# lid.net
KiCad netlist of a schematic drawn in EAGLE
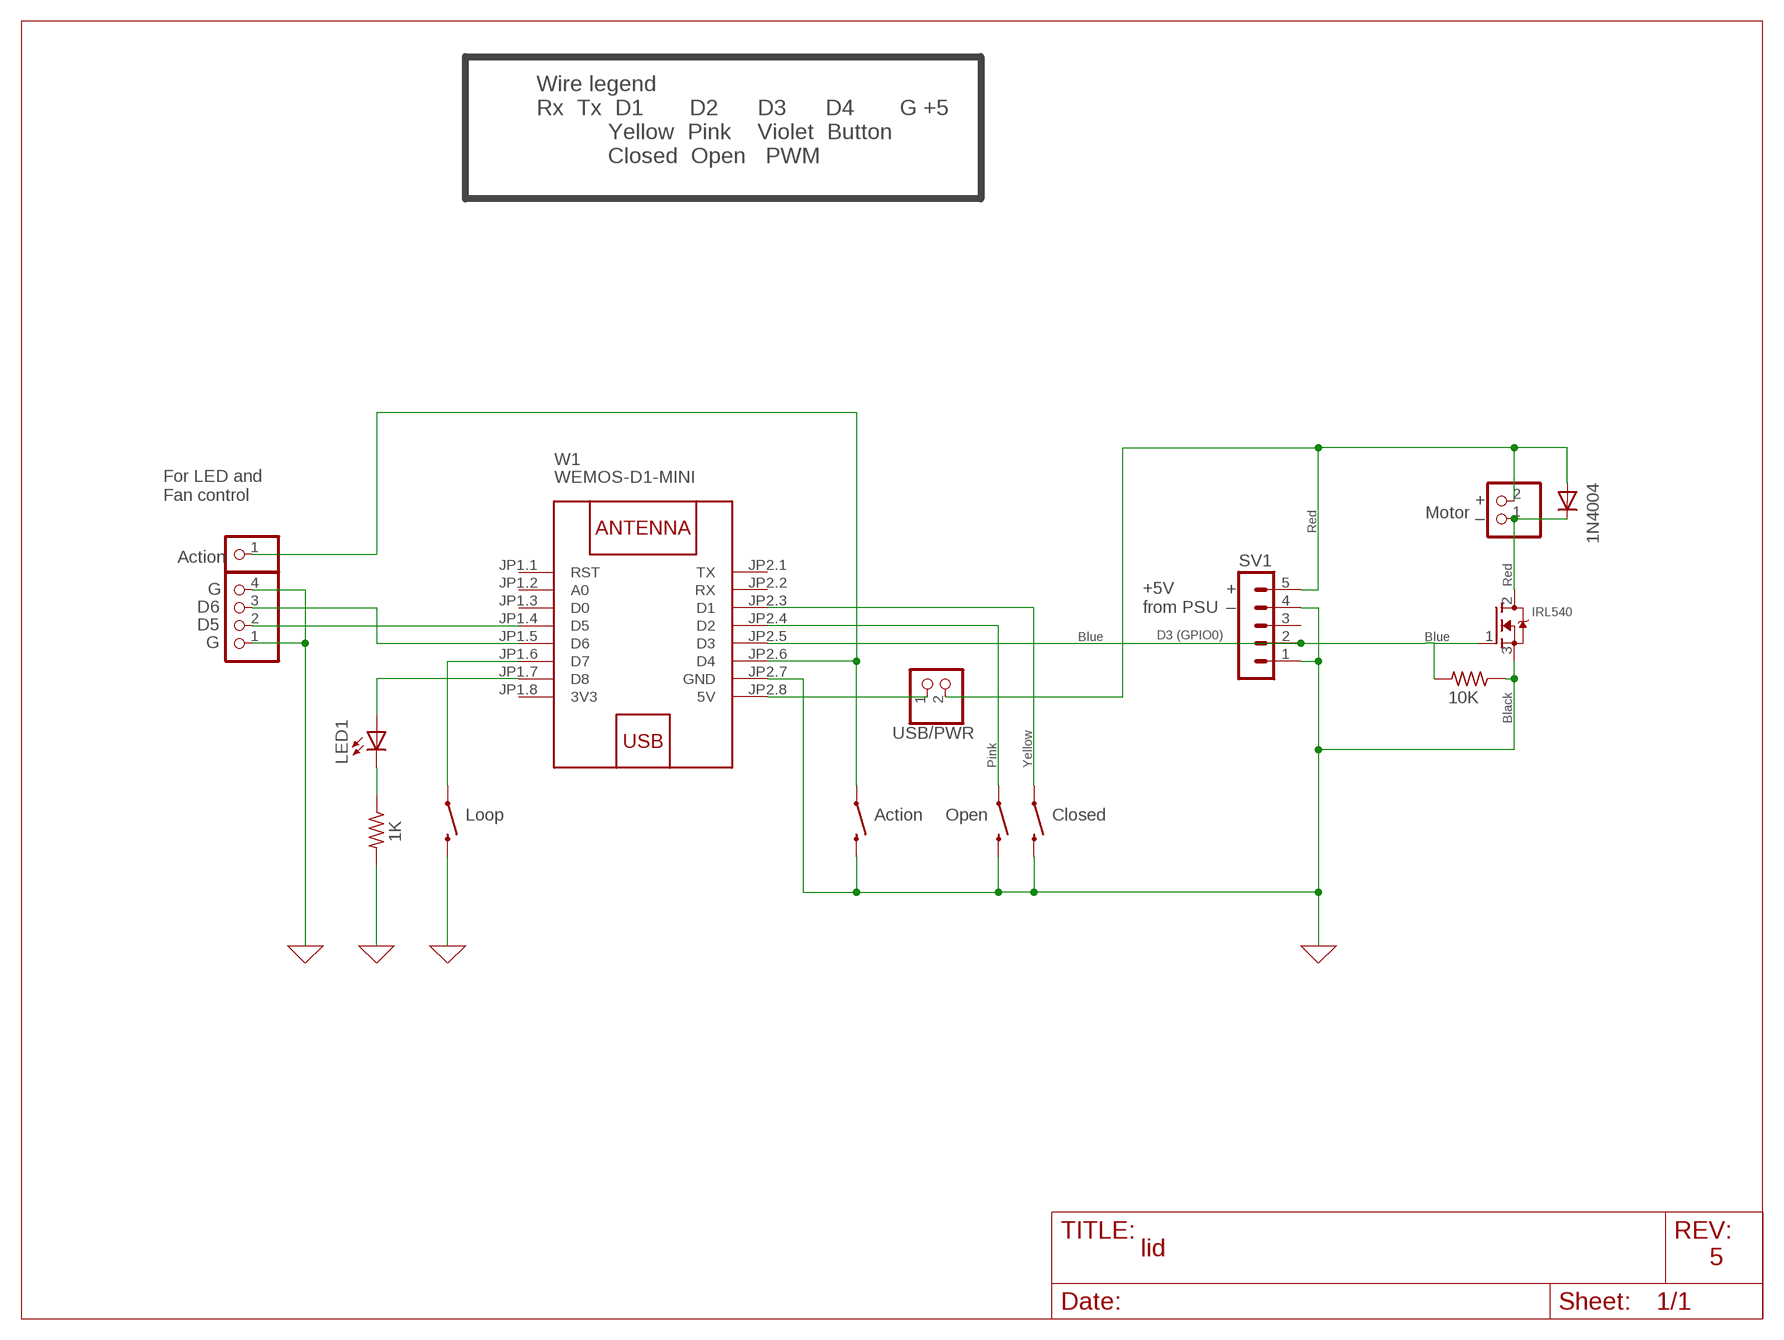
[diagram p0: schematic, sheet 1]

(export (version "E")
  (design (tool "Eeschema 10.0.6"))
  (components
    (comp (ref "ACTION")
      (value "MOMENTARY-SWITCH-SPST-PTH-6.0MM")
      (footprint "eagle-import:TACTILE_SWITCH_PTH_6.0MM")
      (libsource (lib "eagle-import") (part "MOMENTARY-SWITCH-SPST-PTH-6.0MM"))
    )
    (comp (ref "ACTION1")
      (value "MOMENTARY-SWITCH-SPST-PTH-6.0MM")
      (footprint "eagle-import:TACTILE_SWITCH_PTH_6.0MM")
      (libsource (lib "eagle-import") (part "MOMENTARY-SWITCH-SPST-PTH-6.0MM"))
    )
    (comp (ref "D1")
      (value "1N4004")
      (footprint "eagle-import:DO41-10")
      (libsource (lib "eagle-import") (part "1N4004"))
    )
    (comp (ref "JP1")
      (value "PINHD-1X1")
      (footprint "eagle-import:1X01")
      (libsource (lib "eagle-import") (part "PINHD-1X1"))
    )
    (comp (ref "JP3")
      (value "PINHD-1X2")
      (footprint "eagle-import:1X02")
      (libsource (lib "eagle-import") (part "PINHD-1X2"))
    )
    (comp (ref "JP4")
      (value "PINHD-1X4")
      (footprint "eagle-import:1X04")
      (libsource (lib "eagle-import") (part "PINHD-1X4"))
    )
    (comp (ref "LED1")
      (value "LED5MM")
      (footprint "eagle-import:LED5MM")
      (libsource (lib "eagle-import") (part "LED5MM"))
    )
    (comp (ref "Q1")
      (value "IRL540")
      (footprint "eagle-import:TO220V")
      (libsource (lib "eagle-import") (part "MOSFET-NGDS_TO220V"))
    )
    (comp (ref "R1")
      (value "1K")
      (footprint "eagle-import:0207_10")
      (libsource (lib "eagle-import") (part "R-US_0207/10"))
    )
    (comp (ref "R4")
      (value "10K")
      (footprint "eagle-import:0207_10")
      (libsource (lib "eagle-import") (part "R-US_0207/10"))
    )
    (comp (ref "S1")
      (value "MOMENTARY-SWITCH-SPST-PTH-6.0MM")
      (footprint "eagle-import:TACTILE_SWITCH_PTH_6.0MM")
      (libsource (lib "eagle-import") (part "MOMENTARY-SWITCH-SPST-PTH-6.0MM"))
    )
    (comp (ref "S2")
      (value "MOMENTARY-SWITCH-SPST-PTH-6.0MM")
      (footprint "eagle-import:TACTILE_SWITCH_PTH_6.0MM")
      (libsource (lib "eagle-import") (part "MOMENTARY-SWITCH-SPST-PTH-6.0MM"))
    )
    (comp (ref "SV1")
      (value "MA05-1")
      (footprint "eagle-import:MA05-1")
      (libsource (lib "eagle-import") (part "MA05-1"))
    )
    (comp (ref "USB/PWR")
      (value "PINHD-1X2")
      (footprint "eagle-import:1X02")
      (libsource (lib "eagle-import") (part "PINHD-1X2"))
    )
    (comp (ref "W1")
      (value "WEMOS-D1-MINI")
      (footprint "eagle-import:WEMOS-D1-MINI")
      (libsource (lib "eagle-import") (part "WEMOS-D1-MINI"))
    )
  )
  (nets
    (net (code "1") (name "/3V3") (class "Default")
      (node (ref "W1") (pin "JP1.8") (pinfunction "3V3_JP1.8") (pintype "power_in"))
    )
    (net (code "2") (name "GND") (class "Default")
      (node (ref "ACTION") (pin "3") (pinfunction "2_3") (pintype "passive"))
      (node (ref "ACTION1") (pin "3") (pinfunction "2_3") (pintype "passive"))
      (node (ref "JP4") (pin "1") (pinfunction "1_1") (pintype "passive"))
      (node (ref "JP4") (pin "4") (pinfunction "4_4") (pintype "passive"))
      (node (ref "Q1") (pin "3") (pinfunction "S_3") (pintype "bidirectional"))
      (node (ref "R1") (pin "2") (pinfunction "2_2") (pintype "passive"))
      (node (ref "R4") (pin "1") (pinfunction "1_1") (pintype "passive"))
      (node (ref "S1") (pin "3") (pinfunction "2_3") (pintype "passive"))
      (node (ref "S2") (pin "3") (pinfunction "2_3") (pintype "passive"))
      (node (ref "SV1") (pin "1") (pinfunction "1_1") (pintype "passive"))
      (node (ref "SV1") (pin "4") (pinfunction "4_4") (pintype "passive"))
      (node (ref "W1") (pin "JP2.7") (pinfunction "GND_JP2.7") (pintype "power_in"))
    )
    (net (code "3") (name "Net-(D1-PadA)") (class "Default")
      (node (ref "D1") (pin "A") (pinfunction "A_A") (pintype "passive"))
      (node (ref "JP3") (pin "2") (pinfunction "2_2") (pintype "passive"))
      (node (ref "SV1") (pin "5") (pinfunction "5_5") (pintype "passive"))
      (node (ref "USB/PWR") (pin "2") (pinfunction "2_2") (pintype "passive"))
    )
    (net (code "4") (name "Net-(LED1-C)") (class "Default")
      (node (ref "LED1") (pin "K") (pinfunction "C_K") (pintype "passive"))
      (node (ref "R1") (pin "1") (pinfunction "1_1") (pintype "passive"))
    )
    (net (code "5") (name "Net-(Q1-D)") (class "Default")
      (node (ref "D1") (pin "C") (pinfunction "C_C") (pintype "passive"))
      (node (ref "JP3") (pin "1") (pinfunction "1_1") (pintype "passive"))
      (node (ref "Q1") (pin "2") (pinfunction "D_2") (pintype "bidirectional"))
    )
    (net (code "6") (name "Net-(Q1-G)") (class "Default")
      (node (ref "Q1") (pin "1") (pinfunction "G_1") (pintype "bidirectional"))
      (node (ref "R4") (pin "2") (pinfunction "2_2") (pintype "passive"))
      (node (ref "SV1") (pin "2") (pinfunction "2_2") (pintype "passive"))
      (node (ref "W1") (pin "JP2.5") (pinfunction "D3_JP2.5") (pintype "bidirectional"))
    )
    (net (code "7") (name "Net-(W1-5V)") (class "Default")
      (node (ref "USB/PWR") (pin "1") (pinfunction "1_1") (pintype "passive"))
      (node (ref "W1") (pin "JP2.8") (pinfunction "5V_JP2.8") (pintype "power_in"))
    )
    (net (code "8") (name "Net-(W1-D1)") (class "Default")
      (node (ref "S2") (pin "1") (pinfunction "1_1") (pintype "passive"))
      (node (ref "W1") (pin "JP2.3") (pinfunction "D1_JP2.3") (pintype "bidirectional"))
    )
    (net (code "9") (name "Net-(W1-D2)") (class "Default")
      (node (ref "S1") (pin "1") (pinfunction "1_1") (pintype "passive"))
      (node (ref "W1") (pin "JP2.4") (pinfunction "D2_JP2.4") (pintype "bidirectional"))
    )
    (net (code "10") (name "Net-(W1-D4)") (class "Default")
      (node (ref "ACTION") (pin "1") (pinfunction "1_1") (pintype "passive"))
      (node (ref "JP1") (pin "1") (pinfunction "1_1") (pintype "passive"))
      (node (ref "W1") (pin "JP2.6") (pinfunction "D4_JP2.6") (pintype "bidirectional"))
    )
    (net (code "11") (name "Net-(W1-D5)") (class "Default")
      (node (ref "JP4") (pin "2") (pinfunction "2_2") (pintype "passive"))
      (node (ref "W1") (pin "JP1.4") (pinfunction "D5_JP1.4") (pintype "bidirectional"))
    )
    (net (code "12") (name "Net-(W1-D6)") (class "Default")
      (node (ref "JP4") (pin "3") (pinfunction "3_3") (pintype "passive"))
      (node (ref "W1") (pin "JP1.5") (pinfunction "D6_JP1.5") (pintype "bidirectional"))
    )
    (net (code "13") (name "Net-(W1-D7)") (class "Default")
      (node (ref "ACTION1") (pin "1") (pinfunction "1_1") (pintype "passive"))
      (node (ref "W1") (pin "JP1.6") (pinfunction "D7_JP1.6") (pintype "bidirectional"))
    )
    (net (code "14") (name "Net-(W1-D8)") (class "Default")
      (node (ref "LED1") (pin "A") (pinfunction "A_A") (pintype "passive"))
      (node (ref "W1") (pin "JP1.7") (pinfunction "D8_JP1.7") (pintype "bidirectional"))
    )
    (net (code "15") (name "unconnected-(SV1-Pad3)") (class "Default")
      (node (ref "SV1") (pin "3") (pinfunction "3_3") (pintype "passive"))
    )
    (net (code "16") (name "unconnected-(W1-A0-PadJP1.2)") (class "Default")
      (node (ref "W1") (pin "JP1.2") (pinfunction "A0_JP1.2") (pintype "bidirectional"))
    )
    (net (code "17") (name "unconnected-(W1-D0-PadJP1.3)") (class "Default")
      (node (ref "W1") (pin "JP1.3") (pinfunction "D0_JP1.3") (pintype "bidirectional"))
    )
    (net (code "18") (name "unconnected-(W1-RST-PadJP1.1)") (class "Default")
      (node (ref "W1") (pin "JP1.1") (pinfunction "RST_JP1.1") (pintype "bidirectional"))
    )
    (net (code "19") (name "unconnected-(W1-RX-PadJP2.2)") (class "Default")
      (node (ref "W1") (pin "JP2.2") (pinfunction "RX_JP2.2") (pintype "bidirectional"))
    )
    (net (code "20") (name "unconnected-(W1-TX-PadJP2.1)") (class "Default")
      (node (ref "W1") (pin "JP2.1") (pinfunction "TX_JP2.1") (pintype "bidirectional"))
    )
  )
)
